# 4_Interfaces.net
KiCad netlist of a schematic drawn in Altium Designer
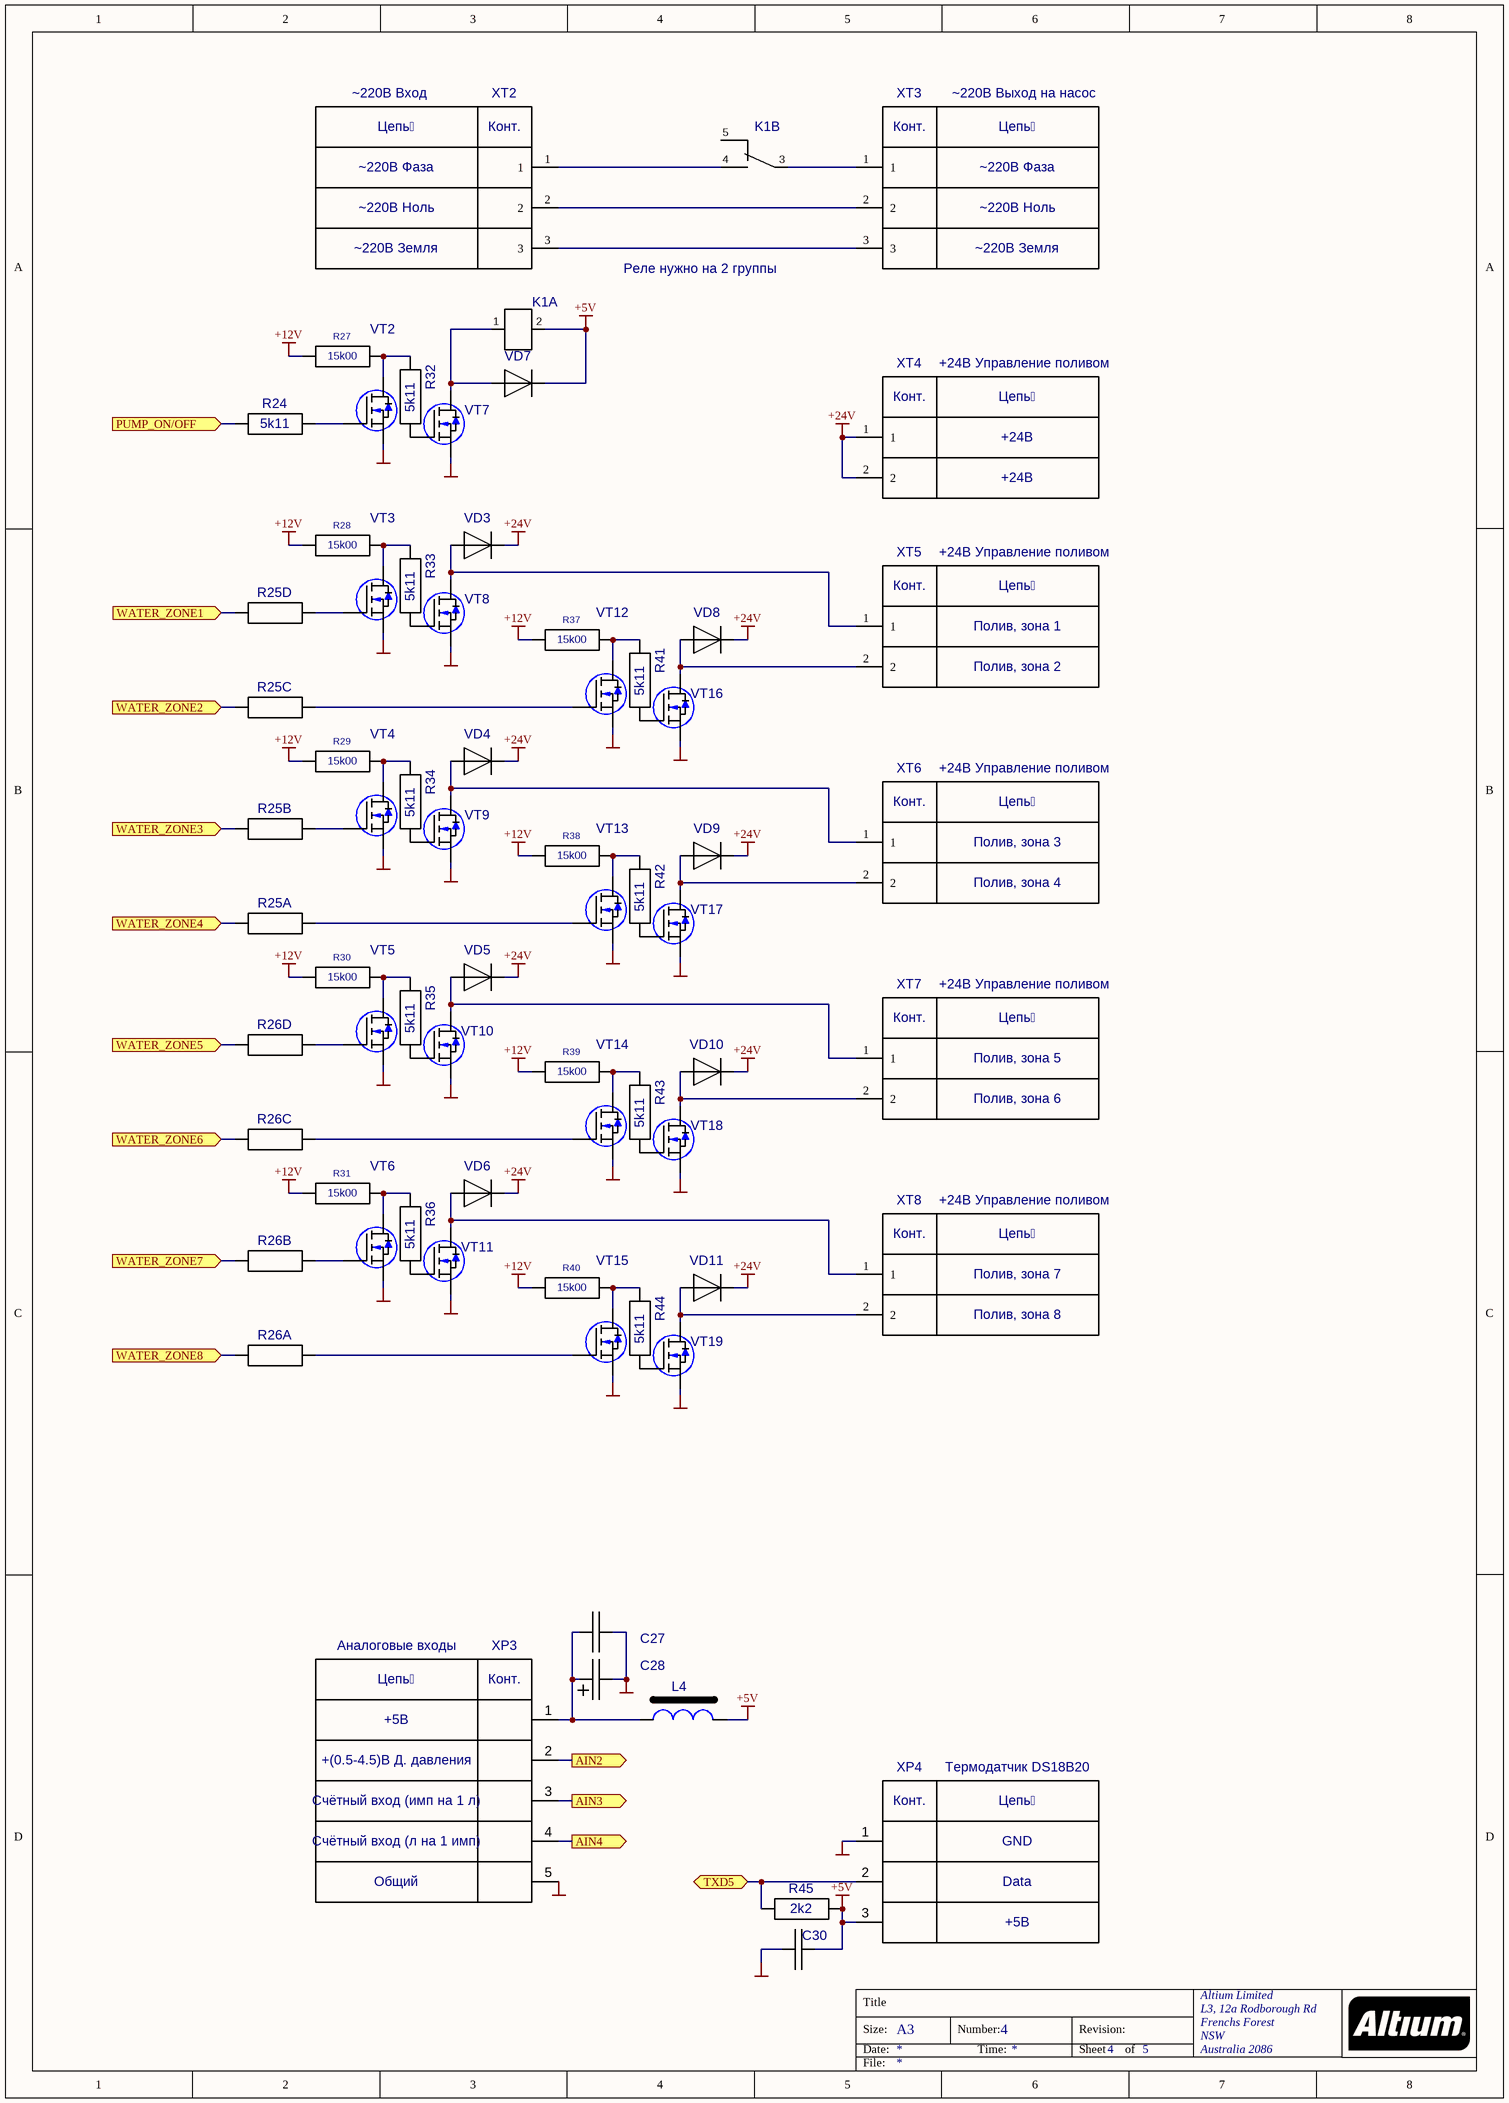
[diagram p0: 4 Interfaces.SchDoc]

(export (version "E")
  (design (tool "Eeschema 10.0.6"))
  (components
    (comp (ref "C27")
      (value "C0402")
      (footprint "конденсаторы:0402_CAP")
      (libsource (lib "Com via Eth") (part "C0402"))
    )
    (comp (ref "C28")
      (value "10.0x16V")
      (footprint "конденсаторы:TC3216-A")
      (description "TC3216-A")
      (libsource (lib "*") (part "TC3216-A"))
    )
    (comp (ref "C30")
      (value "C0402")
      (footprint "конденсаторы:0402_CAP")
      (libsource (lib "Com via Eth") (part "C0402"))
    )
    (comp (ref "K1")
      (value "TRV-5VDC-SC-CD")
      (footprint "TRV-5VDC-SC-CD")
      (libsource (lib "Реле") (part "TRV-5VDC-SC-CD"))
    )
    (comp (ref "L4")
      (value "100µH LQH43CN101K")
      (footprint "LQH43")
      (description "LQH43, 1812")
      (libsource (lib "дроссели и трансы") (part "LQH43"))
    )
    (comp (ref "R24")
      (value "5k11")
      (footprint "резисторы:0603_RES")
      (description "R0603")
      (libsource (lib "*") (part "R0603"))
    )
    (comp (ref "R25")
      (value "4k7 CAT16-472J4")
      (footprint "резисторы:CAT16")
      (description "CAT16-472J4")
      (libsource (lib "резисторы") (part "CAT16"))
    )
    (comp (ref "R26")
      (value "4k7 CAT16-472J4")
      (footprint "резисторы:CAT16")
      (description "CAT16-472J4")
      (libsource (lib "резисторы") (part "CAT16"))
    )
    (comp (ref "R27")
      (value "15k00")
      (footprint "резисторы:0603_RES")
      (description "R0603")
      (libsource (lib "резисторы") (part "R0603"))
    )
    (comp (ref "R28")
      (value "15k00")
      (footprint "резисторы:0603_RES")
      (description "R0603")
      (libsource (lib "резисторы") (part "R0603"))
    )
    (comp (ref "R29")
      (value "15k00")
      (footprint "резисторы:0603_RES")
      (description "R0603")
      (libsource (lib "резисторы") (part "R0603"))
    )
    (comp (ref "R30")
      (value "15k00")
      (footprint "резисторы:0603_RES")
      (description "R0603")
      (libsource (lib "резисторы") (part "R0603"))
    )
    (comp (ref "R31")
      (value "15k00")
      (footprint "резисторы:0603_RES")
      (description "R0603")
      (libsource (lib "резисторы") (part "R0603"))
    )
    (comp (ref "R32")
      (value "5k11")
      (footprint "резисторы:0603_RES")
      (description "R0603")
      (libsource (lib "*") (part "R0603"))
    )
    (comp (ref "R33")
      (value "5k11")
      (footprint "резисторы:0603_RES")
      (description "R0603")
      (libsource (lib "*") (part "R0603"))
    )
    (comp (ref "R34")
      (value "5k11")
      (footprint "резисторы:0603_RES")
      (description "R0603")
      (libsource (lib "*") (part "R0603"))
    )
    (comp (ref "R35")
      (value "5k11")
      (footprint "резисторы:0603_RES")
      (description "R0603")
      (libsource (lib "*") (part "R0603"))
    )
    (comp (ref "R36")
      (value "5k11")
      (footprint "резисторы:0603_RES")
      (description "R0603")
      (libsource (lib "*") (part "R0603"))
    )
    (comp (ref "R37")
      (value "15k00")
      (footprint "резисторы:0603_RES")
      (description "R0603")
      (libsource (lib "резисторы") (part "R0603"))
    )
    (comp (ref "R38")
      (value "15k00")
      (footprint "резисторы:0603_RES")
      (description "R0603")
      (libsource (lib "резисторы") (part "R0603"))
    )
    (comp (ref "R39")
      (value "15k00")
      (footprint "резисторы:0603_RES")
      (description "R0603")
      (libsource (lib "резисторы") (part "R0603"))
    )
    (comp (ref "R40")
      (value "15k00")
      (footprint "резисторы:0603_RES")
      (description "R0603")
      (libsource (lib "резисторы") (part "R0603"))
    )
    (comp (ref "R41")
      (value "5k11")
      (footprint "резисторы:0603_RES")
      (description "R0603")
      (libsource (lib "*") (part "R0603"))
    )
    (comp (ref "R42")
      (value "5k11")
      (footprint "резисторы:0603_RES")
      (description "R0603")
      (libsource (lib "*") (part "R0603"))
    )
    (comp (ref "R43")
      (value "5k11")
      (footprint "резисторы:0603_RES")
      (description "R0603")
      (libsource (lib "*") (part "R0603"))
    )
    (comp (ref "R44")
      (value "5k11")
      (footprint "резисторы:0603_RES")
      (description "R0603")
      (libsource (lib "*") (part "R0603"))
    )
    (comp (ref "R45")
      (value "2k2")
      (footprint "резисторы:0603_RES")
      (description "R0603")
      (libsource (lib "*") (part "R0603"))
    )
    (comp (ref "VD3") (value "ES1D") (footprint "диоды:SMA") (libsource (lib "диоды") (part "ES1D")))
    (comp (ref "VD4") (value "ES1D") (footprint "диоды:SMA") (libsource (lib "диоды") (part "ES1D")))
    (comp (ref "VD5") (value "ES1D") (footprint "диоды:SMA") (libsource (lib "диоды") (part "ES1D")))
    (comp (ref "VD6") (value "ES1D") (footprint "диоды:SMA") (libsource (lib "диоды") (part "ES1D")))
    (comp (ref "VD7") (value "ES1D") (footprint "диоды:SMA") (libsource (lib "диоды") (part "ES1D")))
    (comp (ref "VD8") (value "ES1D") (footprint "диоды:SMA") (libsource (lib "диоды") (part "ES1D")))
    (comp (ref "VD9") (value "ES1D") (footprint "диоды:SMA") (libsource (lib "диоды") (part "ES1D")))
    (comp (ref "VD10") (value "ES1D") (footprint "диоды:SMA") (libsource (lib "диоды") (part "ES1D")))
    (comp (ref "VD11") (value "ES1D") (footprint "диоды:SMA") (libsource (lib "диоды") (part "ES1D")))
    (comp (ref "VT2")
      (value "MMBF170Q-7-F")
      (footprint "транзисторы:SOT-23 MOSFET")
      (libsource (lib "транзисторы") (part "MMBF170"))
    )
    (comp (ref "VT3")
      (value "MMBF170Q-7-F")
      (footprint "транзисторы:SOT-23 MOSFET")
      (libsource (lib "транзисторы") (part "MMBF170"))
    )
    (comp (ref "VT4")
      (value "MMBF170Q-7-F")
      (footprint "транзисторы:SOT-23 MOSFET")
      (libsource (lib "транзисторы") (part "MMBF170"))
    )
    (comp (ref "VT5")
      (value "MMBF170Q-7-F")
      (footprint "транзисторы:SOT-23 MOSFET")
      (libsource (lib "транзисторы") (part "MMBF170"))
    )
    (comp (ref "VT6")
      (value "MMBF170Q-7-F")
      (footprint "транзисторы:SOT-23 MOSFET")
      (libsource (lib "транзисторы") (part "MMBF170"))
    )
    (comp (ref "VT7")
      (value "AO3400A")
      (footprint "транзисторы:SOT-23 MOSFET")
      (libsource (lib "транзисторы") (part "IRLML2060TRPBF"))
    )
    (comp (ref "VT8")
      (value "AO3400A")
      (footprint "транзисторы:SOT-23 MOSFET")
      (libsource (lib "транзисторы") (part "IRLML2060TRPBF"))
    )
    (comp (ref "VT9")
      (value "AO3400A")
      (footprint "транзисторы:SOT-23 MOSFET")
      (libsource (lib "транзисторы") (part "IRLML2060TRPBF"))
    )
    (comp (ref "VT10")
      (value "AO3400A")
      (footprint "транзисторы:SOT-23 MOSFET")
      (libsource (lib "транзисторы") (part "IRLML2060TRPBF"))
    )
    (comp (ref "VT11")
      (value "AO3400A")
      (footprint "транзисторы:SOT-23 MOSFET")
      (libsource (lib "транзисторы") (part "IRLML2060TRPBF"))
    )
    (comp (ref "VT12")
      (value "MMBF170Q-7-F")
      (footprint "транзисторы:SOT-23 MOSFET")
      (libsource (lib "транзисторы") (part "MMBF170"))
    )
    (comp (ref "VT13")
      (value "MMBF170Q-7-F")
      (footprint "транзисторы:SOT-23 MOSFET")
      (libsource (lib "транзисторы") (part "MMBF170"))
    )
    (comp (ref "VT14")
      (value "MMBF170Q-7-F")
      (footprint "транзисторы:SOT-23 MOSFET")
      (libsource (lib "транзисторы") (part "MMBF170"))
    )
    (comp (ref "VT15")
      (value "MMBF170Q-7-F")
      (footprint "транзисторы:SOT-23 MOSFET")
      (libsource (lib "транзисторы") (part "MMBF170"))
    )
    (comp (ref "VT16")
      (value "AO3400A")
      (footprint "транзисторы:SOT-23 MOSFET")
      (libsource (lib "транзисторы") (part "IRLML2060TRPBF"))
    )
    (comp (ref "VT17")
      (value "AO3400A")
      (footprint "транзисторы:SOT-23 MOSFET")
      (libsource (lib "транзисторы") (part "IRLML2060TRPBF"))
    )
    (comp (ref "VT18")
      (value "AO3400A")
      (footprint "транзисторы:SOT-23 MOSFET")
      (libsource (lib "транзисторы") (part "IRLML2060TRPBF"))
    )
    (comp (ref "VT19")
      (value "AO3400A")
      (footprint "транзисторы:SOT-23 MOSFET")
      (libsource (lib "транзисторы") (part "IRLML2060TRPBF"))
    )
    (comp (ref "XP3") (value "PH-5") (footprint "PH-5") (libsource (lib "разъёмы") (part "PH-5")))
    (comp (ref "XP4") (value "PH-3") (footprint "PH-3") (libsource (lib "разъёмы") (part "PH-3")))
    (comp (ref "XT2")
      (value "XY301VA-5.0-3P-12")
      (footprint "301-031-12")
      (description "Клеммник винтовой, 3-контактный, 5мм, прямой")
      (libsource (lib "разъёмы") (part "301-031-12"))
    )
    (comp (ref "XT3")
      (value "XY301VA-5.0-3P-12")
      (footprint "301-031-12")
      (description "Клеммник винтовой, 3-контактный, 5мм, прямой")
      (libsource (lib "разъёмы") (part "301-031-12"))
    )
    (comp (ref "XT4")
      (value "XY301VA-5.0-2P-12")
      (footprint "разъёмы:301-021-12")
      (description "Клеммник винтовой, 2-контактный, 5мм, прямой")
      (libsource (lib "разъёмы") (part "301-021-12"))
    )
    (comp (ref "XT5")
      (value "XY301VA-5.0-2P-12")
      (footprint "разъёмы:301-021-12")
      (description "Клеммник винтовой, 2-контактный, 5мм, прямой")
      (libsource (lib "разъёмы") (part "301-021-12"))
    )
    (comp (ref "XT6")
      (value "XY301VA-5.0-2P-12")
      (footprint "разъёмы:301-021-12")
      (description "Клеммник винтовой, 2-контактный, 5мм, прямой")
      (libsource (lib "разъёмы") (part "301-021-12"))
    )
    (comp (ref "XT7")
      (value "XY301VA-5.0-2P-12")
      (footprint "разъёмы:301-021-12")
      (description "Клеммник винтовой, 2-контактный, 5мм, прямой")
      (libsource (lib "разъёмы") (part "301-021-12"))
    )
    (comp (ref "XT8")
      (value "XY301VA-5.0-2P-12")
      (footprint "разъёмы:301-021-12")
      (description "Клеммник винтовой, 2-контактный, 5мм, прямой")
      (libsource (lib "разъёмы") (part "301-021-12"))
    )
  )
  (nets
    (net (code "1") (name "+5V") (class "Default")
      (node (ref "C30") (pin "1") (pinfunction "1_1") (pintype "passive"))
      (node (ref "K1") (pin "2") (pintype "passive"))
      (node (ref "L4") (pin "2") (pinfunction "2_2") (pintype "passive"))
      (node (ref "R45") (pin "2") (pinfunction "2_2") (pintype "passive"))
      (node (ref "VD7") (pin "2") (pinfunction "K_2") (pintype "passive"))
      (node (ref "XP4") (pin "3") (pintype "passive"))
    )
    (net (code "2") (name "+12V") (class "Default")
      (node (ref "R27") (pin "1") (pinfunction "1_1") (pintype "passive"))
      (node (ref "R28") (pin "1") (pinfunction "1_1") (pintype "passive"))
      (node (ref "R29") (pin "1") (pinfunction "1_1") (pintype "passive"))
      (node (ref "R30") (pin "1") (pinfunction "1_1") (pintype "passive"))
      (node (ref "R31") (pin "1") (pinfunction "1_1") (pintype "passive"))
      (node (ref "R37") (pin "1") (pinfunction "1_1") (pintype "passive"))
      (node (ref "R38") (pin "1") (pinfunction "1_1") (pintype "passive"))
      (node (ref "R39") (pin "1") (pinfunction "1_1") (pintype "passive"))
      (node (ref "R40") (pin "1") (pinfunction "1_1") (pintype "passive"))
    )
    (net (code "3") (name "+24V") (class "Default")
      (node (ref "VD10") (pin "2") (pinfunction "K_2") (pintype "passive"))
      (node (ref "VD11") (pin "2") (pinfunction "K_2") (pintype "passive"))
      (node (ref "VD3") (pin "2") (pinfunction "K_2") (pintype "passive"))
      (node (ref "VD4") (pin "2") (pinfunction "K_2") (pintype "passive"))
      (node (ref "VD5") (pin "2") (pinfunction "K_2") (pintype "passive"))
      (node (ref "VD6") (pin "2") (pinfunction "K_2") (pintype "passive"))
      (node (ref "VD8") (pin "2") (pinfunction "K_2") (pintype "passive"))
      (node (ref "VD9") (pin "2") (pinfunction "K_2") (pintype "passive"))
      (node (ref "XT4") (pin "1") (pinfunction "1_1") (pintype "passive"))
      (node (ref "XT4") (pin "2") (pinfunction "2_2") (pintype "passive"))
    )
    (net (code "4") (name "/AIN2") (class "Default") (node (ref "XP3") (pin "2") (pintype "passive")))
    (net (code "5") (name "/AIN3") (class "Default") (node (ref "XP3") (pin "3") (pintype "passive")))
    (net (code "6") (name "/AIN4") (class "Default") (node (ref "XP3") (pin "4") (pintype "passive")))
    (net (code "7") (name "/PUMP_ON{slash}OFF") (class "Default")
      (node (ref "R24") (pin "1") (pinfunction "1_1") (pintype "passive"))
    )
    (net (code "8") (name "/TXD5") (class "Default")
      (node (ref "R45") (pin "1") (pinfunction "1_1") (pintype "passive"))
      (node (ref "XP4") (pin "2") (pintype "passive"))
    )
    (net (code "9") (name "/WATER_ZONE1") (class "Default")
      (node (ref "R25") (pin "7") (pinfunction "1_7") (pintype "passive"))
    )
    (net (code "10") (name "/WATER_ZONE2") (class "Default")
      (node (ref "R25") (pin "5") (pinfunction "1_5") (pintype "passive"))
    )
    (net (code "11") (name "/WATER_ZONE3") (class "Default")
      (node (ref "R25") (pin "3") (pinfunction "1_3") (pintype "passive"))
    )
    (net (code "12") (name "/WATER_ZONE4") (class "Default")
      (node (ref "R25") (pin "1") (pinfunction "1_1") (pintype "passive"))
    )
    (net (code "13") (name "/WATER_ZONE5") (class "Default")
      (node (ref "R26") (pin "7") (pinfunction "1_7") (pintype "passive"))
    )
    (net (code "14") (name "/WATER_ZONE6") (class "Default")
      (node (ref "R26") (pin "5") (pinfunction "1_5") (pintype "passive"))
    )
    (net (code "15") (name "/WATER_ZONE7") (class "Default")
      (node (ref "R26") (pin "3") (pinfunction "1_3") (pintype "passive"))
    )
    (net (code "16") (name "/WATER_ZONE8") (class "Default")
      (node (ref "R26") (pin "1") (pinfunction "1_1") (pintype "passive"))
    )
    (net (code "17") (name "GND") (class "Default")
      (node (ref "C27") (pin "2") (pinfunction "2_2") (pintype "passive"))
      (node (ref "C28") (pin "2") (pinfunction "2_2") (pintype "passive"))
      (node (ref "C30") (pin "2") (pinfunction "2_2") (pintype "passive"))
      (node (ref "VT10") (pin "2") (pinfunction "S_2") (pintype "passive"))
      (node (ref "VT11") (pin "2") (pinfunction "S_2") (pintype "passive"))
      (node (ref "VT12") (pin "2") (pinfunction "S_2") (pintype "passive"))
      (node (ref "VT13") (pin "2") (pinfunction "S_2") (pintype "passive"))
      (node (ref "VT14") (pin "2") (pinfunction "S_2") (pintype "passive"))
      (node (ref "VT15") (pin "2") (pinfunction "S_2") (pintype "passive"))
      (node (ref "VT16") (pin "2") (pinfunction "S_2") (pintype "passive"))
      (node (ref "VT17") (pin "2") (pinfunction "S_2") (pintype "passive"))
      (node (ref "VT18") (pin "2") (pinfunction "S_2") (pintype "passive"))
      (node (ref "VT19") (pin "2") (pinfunction "S_2") (pintype "passive"))
      (node (ref "VT2") (pin "2") (pinfunction "S_2") (pintype "passive"))
      (node (ref "VT3") (pin "2") (pinfunction "S_2") (pintype "passive"))
      (node (ref "VT4") (pin "2") (pinfunction "S_2") (pintype "passive"))
      (node (ref "VT5") (pin "2") (pinfunction "S_2") (pintype "passive"))
      (node (ref "VT6") (pin "2") (pinfunction "S_2") (pintype "passive"))
      (node (ref "VT7") (pin "2") (pinfunction "S_2") (pintype "passive"))
      (node (ref "VT8") (pin "2") (pinfunction "S_2") (pintype "passive"))
      (node (ref "VT9") (pin "2") (pinfunction "S_2") (pintype "passive"))
      (node (ref "XP3") (pin "5") (pintype "passive"))
      (node (ref "XP4") (pin "1") (pintype "passive"))
    )
    (net (code "18") (name "Net-(C27-Pad1)") (class "Default")
      (node (ref "C27") (pin "1") (pinfunction "1_1") (pintype "passive"))
      (node (ref "C28") (pin "1") (pinfunction "1_1") (pintype "passive"))
      (node (ref "L4") (pin "1") (pinfunction "1_1") (pintype "passive"))
      (node (ref "XP3") (pin "1") (pintype "passive"))
    )
    (net (code "19") (name "Net-(K1-Pad3)") (class "Default")
      (node (ref "K1") (pin "3") (pintype "passive"))
      (node (ref "XT3") (pin "1") (pinfunction "1_1") (pintype "passive"))
    )
    (net (code "20") (name "Net-(K1-Pad4)") (class "Default")
      (node (ref "K1") (pin "4") (pintype "passive"))
      (node (ref "XT2") (pin "1") (pinfunction "1_1") (pintype "passive"))
    )
    (net (code "21") (name "Net-(R25B-2)") (class "Default")
      (node (ref "R25") (pin "4") (pinfunction "2_4") (pintype "passive"))
      (node (ref "VT4") (pin "1") (pinfunction "G_1") (pintype "passive"))
    )
    (net (code "22") (name "Net-(R25C-2)") (class "Default")
      (node (ref "R25") (pin "6") (pinfunction "2_6") (pintype "passive"))
      (node (ref "VT12") (pin "1") (pinfunction "G_1") (pintype "passive"))
    )
    (net (code "23") (name "Net-(R25D-2)") (class "Default")
      (node (ref "R25") (pin "8") (pinfunction "2_8") (pintype "passive"))
      (node (ref "VT3") (pin "1") (pinfunction "G_1") (pintype "passive"))
    )
    (net (code "24") (name "Net-(R26B-2)") (class "Default")
      (node (ref "R26") (pin "4") (pinfunction "2_4") (pintype "passive"))
      (node (ref "VT6") (pin "1") (pinfunction "G_1") (pintype "passive"))
    )
    (net (code "25") (name "Net-(R26C-2)") (class "Default")
      (node (ref "R26") (pin "6") (pinfunction "2_6") (pintype "passive"))
      (node (ref "VT14") (pin "1") (pinfunction "G_1") (pintype "passive"))
    )
    (net (code "26") (name "Net-(R26D-2)") (class "Default")
      (node (ref "R26") (pin "8") (pinfunction "2_8") (pintype "passive"))
      (node (ref "VT5") (pin "1") (pinfunction "G_1") (pintype "passive"))
    )
    (net (code "27") (name "Net-(VD3-A)") (class "Default")
      (node (ref "VD3") (pin "1") (pinfunction "A_1") (pintype "passive"))
      (node (ref "VT8") (pin "3") (pinfunction "D_3") (pintype "passive"))
      (node (ref "XT5") (pin "1") (pinfunction "1_1") (pintype "passive"))
    )
    (net (code "28") (name "Net-(VD4-A)") (class "Default")
      (node (ref "VD4") (pin "1") (pinfunction "A_1") (pintype "passive"))
      (node (ref "VT9") (pin "3") (pinfunction "D_3") (pintype "passive"))
      (node (ref "XT6") (pin "1") (pinfunction "1_1") (pintype "passive"))
    )
    (net (code "29") (name "Net-(VD5-A)") (class "Default")
      (node (ref "VD5") (pin "1") (pinfunction "A_1") (pintype "passive"))
      (node (ref "VT10") (pin "3") (pinfunction "D_3") (pintype "passive"))
      (node (ref "XT7") (pin "1") (pinfunction "1_1") (pintype "passive"))
    )
    (net (code "30") (name "Net-(VD6-A)") (class "Default")
      (node (ref "VD6") (pin "1") (pinfunction "A_1") (pintype "passive"))
      (node (ref "VT11") (pin "3") (pinfunction "D_3") (pintype "passive"))
      (node (ref "XT8") (pin "1") (pinfunction "1_1") (pintype "passive"))
    )
    (net (code "31") (name "Net-(VD7-A)") (class "Default")
      (node (ref "K1") (pin "1") (pintype "passive"))
      (node (ref "VD7") (pin "1") (pinfunction "A_1") (pintype "passive"))
      (node (ref "VT7") (pin "3") (pinfunction "D_3") (pintype "passive"))
    )
    (net (code "32") (name "Net-(VD8-A)") (class "Default")
      (node (ref "VD8") (pin "1") (pinfunction "A_1") (pintype "passive"))
      (node (ref "VT16") (pin "3") (pinfunction "D_3") (pintype "passive"))
      (node (ref "XT5") (pin "2") (pinfunction "2_2") (pintype "passive"))
    )
    (net (code "33") (name "Net-(VD9-A)") (class "Default")
      (node (ref "VD9") (pin "1") (pinfunction "A_1") (pintype "passive"))
      (node (ref "VT17") (pin "3") (pinfunction "D_3") (pintype "passive"))
      (node (ref "XT6") (pin "2") (pinfunction "2_2") (pintype "passive"))
    )
    (net (code "34") (name "Net-(VD10-A)") (class "Default")
      (node (ref "VD10") (pin "1") (pinfunction "A_1") (pintype "passive"))
      (node (ref "VT18") (pin "3") (pinfunction "D_3") (pintype "passive"))
      (node (ref "XT7") (pin "2") (pinfunction "2_2") (pintype "passive"))
    )
    (net (code "35") (name "Net-(VD11-A)") (class "Default")
      (node (ref "VD11") (pin "1") (pinfunction "A_1") (pintype "passive"))
      (node (ref "VT19") (pin "3") (pinfunction "D_3") (pintype "passive"))
      (node (ref "XT8") (pin "2") (pinfunction "2_2") (pintype "passive"))
    )
    (net (code "36") (name "Net-(VT2-D)") (class "Default")
      (node (ref "R27") (pin "2") (pinfunction "2_2") (pintype "passive"))
      (node (ref "R32") (pin "2") (pinfunction "2_2") (pintype "passive"))
      (node (ref "VT2") (pin "3") (pinfunction "D_3") (pintype "passive"))
    )
    (net (code "37") (name "Net-(VT2-G)") (class "Default")
      (node (ref "R24") (pin "2") (pinfunction "2_2") (pintype "passive"))
      (node (ref "VT2") (pin "1") (pinfunction "G_1") (pintype "passive"))
    )
    (net (code "38") (name "Net-(VT3-D)") (class "Default")
      (node (ref "R28") (pin "2") (pinfunction "2_2") (pintype "passive"))
      (node (ref "R33") (pin "2") (pinfunction "2_2") (pintype "passive"))
      (node (ref "VT3") (pin "3") (pinfunction "D_3") (pintype "passive"))
    )
    (net (code "39") (name "Net-(VT4-D)") (class "Default")
      (node (ref "R29") (pin "2") (pinfunction "2_2") (pintype "passive"))
      (node (ref "R34") (pin "2") (pinfunction "2_2") (pintype "passive"))
      (node (ref "VT4") (pin "3") (pinfunction "D_3") (pintype "passive"))
    )
    (net (code "40") (name "Net-(VT5-D)") (class "Default")
      (node (ref "R30") (pin "2") (pinfunction "2_2") (pintype "passive"))
      (node (ref "R35") (pin "2") (pinfunction "2_2") (pintype "passive"))
      (node (ref "VT5") (pin "3") (pinfunction "D_3") (pintype "passive"))
    )
    (net (code "41") (name "Net-(VT6-D)") (class "Default")
      (node (ref "R31") (pin "2") (pinfunction "2_2") (pintype "passive"))
      (node (ref "R36") (pin "2") (pinfunction "2_2") (pintype "passive"))
      (node (ref "VT6") (pin "3") (pinfunction "D_3") (pintype "passive"))
    )
    (net (code "42") (name "Net-(VT7-G)") (class "Default")
      (node (ref "R32") (pin "1") (pinfunction "1_1") (pintype "passive"))
      (node (ref "VT7") (pin "1") (pinfunction "G_1") (pintype "passive"))
    )
    (net (code "43") (name "Net-(VT8-G)") (class "Default")
      (node (ref "R33") (pin "1") (pinfunction "1_1") (pintype "passive"))
      (node (ref "VT8") (pin "1") (pinfunction "G_1") (pintype "passive"))
    )
    (net (code "44") (name "Net-(VT9-G)") (class "Default")
      (node (ref "R34") (pin "1") (pinfunction "1_1") (pintype "passive"))
      (node (ref "VT9") (pin "1") (pinfunction "G_1") (pintype "passive"))
    )
    (net (code "45") (name "Net-(VT10-G)") (class "Default")
      (node (ref "R35") (pin "1") (pinfunction "1_1") (pintype "passive"))
      (node (ref "VT10") (pin "1") (pinfunction "G_1") (pintype "passive"))
    )
    (net (code "46") (name "Net-(VT11-G)") (class "Default")
      (node (ref "R36") (pin "1") (pinfunction "1_1") (pintype "passive"))
      (node (ref "VT11") (pin "1") (pinfunction "G_1") (pintype "passive"))
    )
    (net (code "47") (name "Net-(VT12-D)") (class "Default")
      (node (ref "R37") (pin "2") (pinfunction "2_2") (pintype "passive"))
      (node (ref "R41") (pin "2") (pinfunction "2_2") (pintype "passive"))
      (node (ref "VT12") (pin "3") (pinfunction "D_3") (pintype "passive"))
    )
    (net (code "48") (name "Net-(VT13-D)") (class "Default")
      (node (ref "R38") (pin "2") (pinfunction "2_2") (pintype "passive"))
      (node (ref "R42") (pin "2") (pinfunction "2_2") (pintype "passive"))
      (node (ref "VT13") (pin "3") (pinfunction "D_3") (pintype "passive"))
    )
    (net (code "49") (name "Net-(VT13-G)") (class "Default")
      (node (ref "R25") (pin "2") (pinfunction "2_2") (pintype "passive"))
      (node (ref "VT13") (pin "1") (pinfunction "G_1") (pintype "passive"))
    )
    (net (code "50") (name "Net-(VT14-D)") (class "Default")
      (node (ref "R39") (pin "2") (pinfunction "2_2") (pintype "passive"))
      (node (ref "R43") (pin "2") (pinfunction "2_2") (pintype "passive"))
      (node (ref "VT14") (pin "3") (pinfunction "D_3") (pintype "passive"))
    )
    (net (code "51") (name "Net-(VT15-D)") (class "Default")
      (node (ref "R40") (pin "2") (pinfunction "2_2") (pintype "passive"))
      (node (ref "R44") (pin "2") (pinfunction "2_2") (pintype "passive"))
      (node (ref "VT15") (pin "3") (pinfunction "D_3") (pintype "passive"))
    )
    (net (code "52") (name "Net-(VT15-G)") (class "Default")
      (node (ref "R26") (pin "2") (pinfunction "2_2") (pintype "passive"))
      (node (ref "VT15") (pin "1") (pinfunction "G_1") (pintype "passive"))
    )
    (net (code "53") (name "Net-(VT16-G)") (class "Default")
      (node (ref "R41") (pin "1") (pinfunction "1_1") (pintype "passive"))
      (node (ref "VT16") (pin "1") (pinfunction "G_1") (pintype "passive"))
    )
    (net (code "54") (name "Net-(VT17-G)") (class "Default")
      (node (ref "R42") (pin "1") (pinfunction "1_1") (pintype "passive"))
      (node (ref "VT17") (pin "1") (pinfunction "G_1") (pintype "passive"))
    )
    (net (code "55") (name "Net-(VT18-G)") (class "Default")
      (node (ref "R43") (pin "1") (pinfunction "1_1") (pintype "passive"))
      (node (ref "VT18") (pin "1") (pinfunction "G_1") (pintype "passive"))
    )
    (net (code "56") (name "Net-(VT19-G)") (class "Default")
      (node (ref "R44") (pin "1") (pinfunction "1_1") (pintype "passive"))
      (node (ref "VT19") (pin "1") (pinfunction "G_1") (pintype "passive"))
    )
    (net (code "57") (name "Net-(XT2-Pad2)") (class "Default")
      (node (ref "XT2") (pin "2") (pinfunction "2_2") (pintype "passive"))
      (node (ref "XT3") (pin "2") (pinfunction "2_2") (pintype "passive"))
    )
    (net (code "58") (name "Net-(XT2-Pad3)") (class "Default")
      (node (ref "XT2") (pin "3") (pinfunction "3_3") (pintype "passive"))
      (node (ref "XT3") (pin "3") (pinfunction "3_3") (pintype "passive"))
    )
    (net (code "59") (name "unconnected-(K1-Pad5)") (class "Default")
      (node (ref "K1") (pin "5") (pintype "passive"))
    )
  )
)
